# Sheet1.net
KiCad netlist of a schematic drawn in Altium Designer
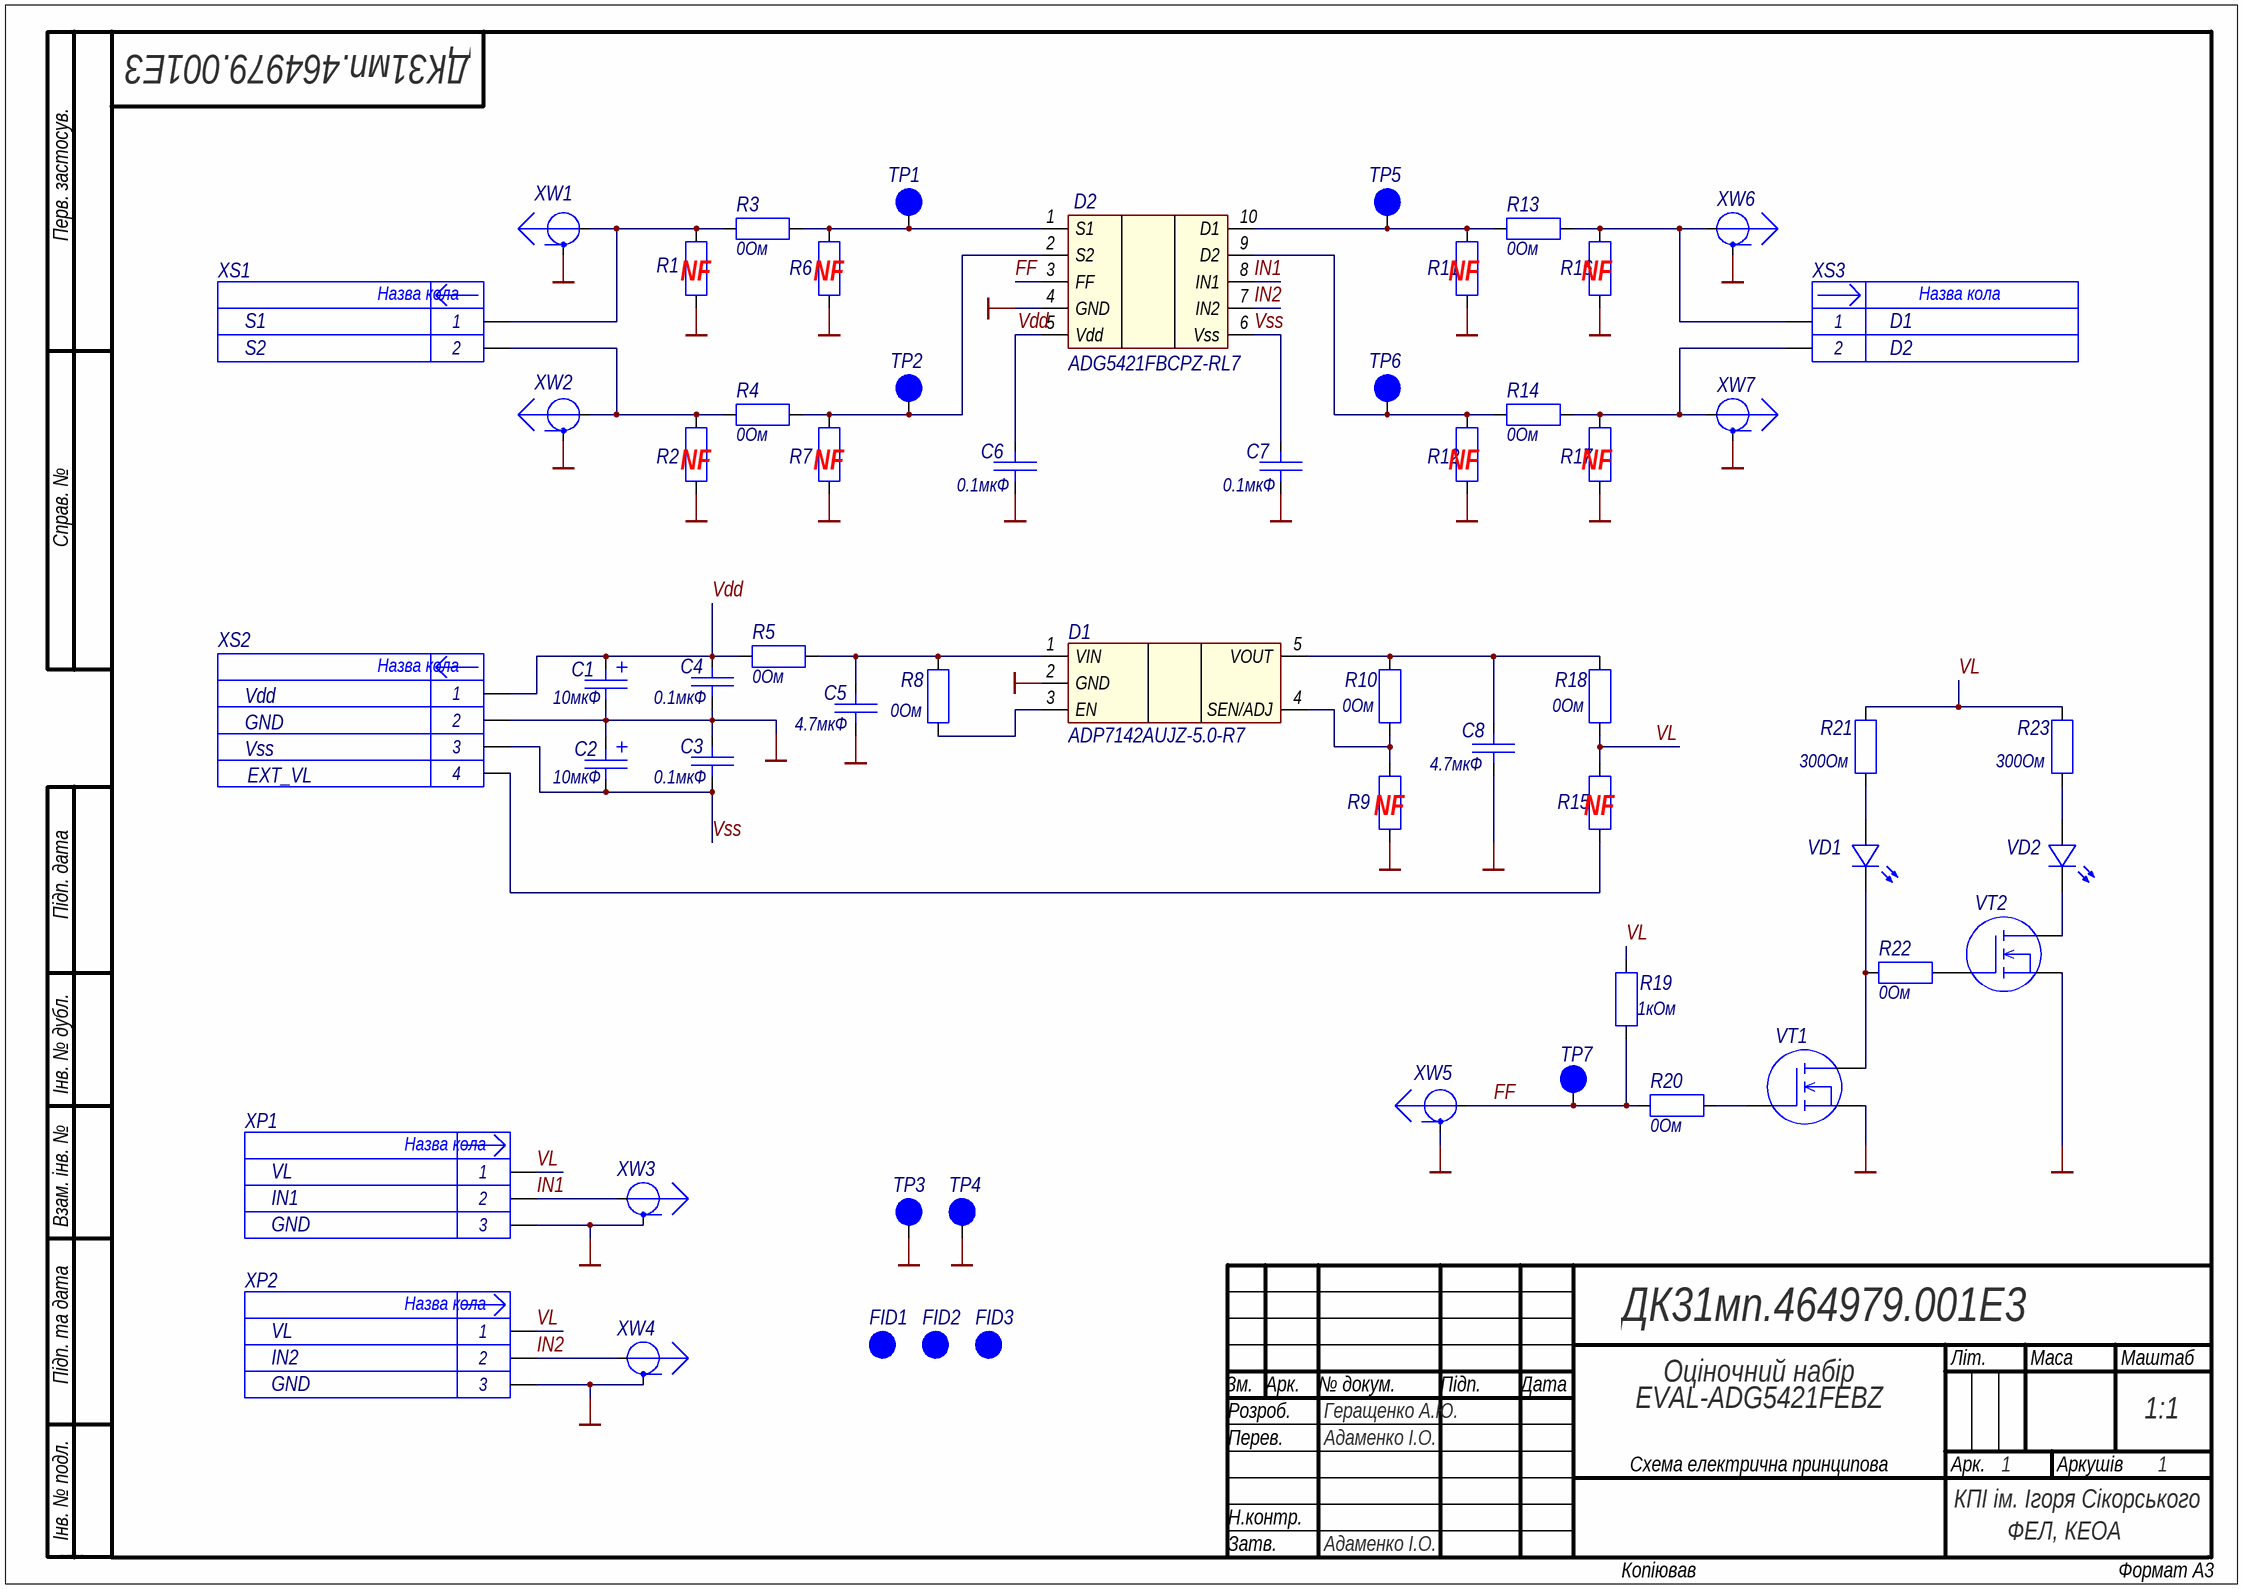
[diagram p0: Sheet1.SchDoc]

(export (version "E")
  (design (tool "Eeschema 10.0.6"))
  (components
    (comp (ref "C1")
      (value "10мкФ")
      (footprint "CAP_TANT_10uF")
      (description "CAP TANT 10UF 10% 50V 2917")
      (fields (field (name "MANUFACTURER") "KYOCERA AVX") (field (name "PART NUMBER") "478-2380-6-ND"))
      (libsource (lib "Schlib1") (part "CAP_TANT_10uF"))
    )
    (comp (ref "C2")
      (value "10мкФ")
      (footprint "CAP_TANT_10uF")
      (description "CAP TANT 10UF 10% 50V 2917")
      (fields (field (name "MANUFACTURER") "KYOCERA AVX") (field (name "PART NUMBER") "478-2380-6-ND"))
      (libsource (lib "Schlib1") (part "CAP_TANT_10uF"))
    )
    (comp (ref "C3")
      (value "0.1мкФ")
      (footprint "CAP_0603_0.1uF")
      (description "CAP CER 0.1UF 50V X7R 0603")
      (fields (field (name "MANUFACTURER") "Murata Electronics") (field (name "PART NUMBER") "490-1519-6-ND"))
      (libsource (lib "Schlib1") (part "CAP_0603_0.1uF"))
    )
    (comp (ref "C4")
      (value "0.1мкФ")
      (footprint "CAP_0603_0.1uF")
      (description "CAP CER 0.1UF 50V X7R 0603")
      (fields (field (name "MANUFACTURER") "Murata Electronics") (field (name "PART NUMBER") "490-1519-6-ND"))
      (libsource (lib "Schlib1") (part "CAP_0603_0.1uF"))
    )
    (comp (ref "C5")
      (value "4.7мкФ")
      (footprint "CAP_0805_4.7uF")
      (description "CAP CER 4.7UF 50V X5R 0805")
      (fields (field (name "MANUFACTURER") "TDK Corporation") (field (name "PART NUMBER") "445-5980-6-ND"))
      (libsource (lib "Schlib1") (part "CAP_0805_4.7uF"))
    )
    (comp (ref "C6")
      (value "0.1мкФ")
      (footprint "CAP_0603_0.1uF")
      (description "CAP CER 0.1UF 50V X7R 0603")
      (fields (field (name "MANUFACTURER") "Murata Electronics") (field (name "PART NUMBER") "490-1519-6-ND"))
      (libsource (lib "Schlib1") (part "CAP_0603_0.1uF"))
    )
    (comp (ref "C7")
      (value "0.1мкФ")
      (footprint "CAP_0603_0.1uF")
      (description "CAP CER 0.1UF 50V X7R 0603")
      (fields (field (name "MANUFACTURER") "Murata Electronics") (field (name "PART NUMBER") "490-1519-6-ND"))
      (libsource (lib "Schlib1") (part "CAP_0603_0.1uF"))
    )
    (comp (ref "C8")
      (value "4.7мкФ")
      (footprint "CAP_0805_4.7uF")
      (description "CAP CER 4.7UF 50V X5R 0805")
      (fields (field (name "MANUFACTURER") "TDK Corporation") (field (name "PART NUMBER") "445-5980-6-ND"))
      (libsource (lib "Schlib1") (part "CAP_0805_4.7uF"))
    )
    (comp (ref "D1")
      (value "ADP7142AUJZ-5.0-R7")
      (footprint "ADP7142AUJZ-5.0-R7")
      (description "IC REG LINEAR 5V 200MA TSOT23-5")
      (fields
        (field (name "MANUFACTURER") "Analog Devices Inc.")
        (field (name "PART NUMBER") "505-ADP7142AUJZ-5.0-R7DKR-ND")
      )
      (libsource (lib "Schlib1") (part "ADP7142AUJZ-5.0-R7"))
    )
    (comp (ref "D2")
      (value "ADG5421FBCPZ-RL7")
      (footprint "ADG5421FBCPZ-RL7")
      (description "IC SW SPST-NCX2 14OHM 10LFCSP")
      (fields
        (field (name "MANUFACTURER") "Analog Devices Inc.")
        (field (name "PART NUMBER") "505-ADG5421FBCPZ-RL7DKR-ND")
      )
      (libsource (lib "Schlib1") (part "ADG5421FBCPZ-RL7"))
    )
    (comp (ref "FID1")
      (value "Fiducial")
      (footprint "FIDUCIAL 1mm")
      (description "Fiducial 1mm Pad")
      (libsource (lib "Schlib1") (part "FIDUCIAL 1mm"))
    )
    (comp (ref "FID2")
      (value "Fiducial")
      (footprint "FIDUCIAL 1mm")
      (description "Fiducial 1mm Pad")
      (libsource (lib "Schlib1") (part "FIDUCIAL 1mm"))
    )
    (comp (ref "FID3")
      (value "Fiducial")
      (footprint "FIDUCIAL 1mm")
      (description "Fiducial 1mm Pad")
      (libsource (lib "Schlib1") (part "FIDUCIAL 1mm"))
    )
    (comp (ref "R1")
      (value "RES_0603 0Ohm")
      (footprint "RES_0603 0Ohm")
      (description "RES 0 OHM 63mW 0603")
      (fields (field (name "MANUFACTURER") "Multicomp") (field (name "PART NUMBER") "MC0603WG00000T5E-TC"))
      (libsource (lib "") (part "RES_0603 0Ohm_2"))
    )
    (comp (ref "R2")
      (value "RES_0603 0Ohm")
      (footprint "RES_0603 0Ohm")
      (description "RES 0 OHM 63mW 0603")
      (fields (field (name "MANUFACTURER") "Multicomp") (field (name "PART NUMBER") "MC0603WG00000T5E-TC"))
      (libsource (lib "") (part "RES_0603 0Ohm_2"))
    )
    (comp (ref "R3")
      (value "0Ом")
      (footprint "RES_0603 0Ohm")
      (description "RES 0 OHM 63mW 0603")
      (fields (field (name "MANUFACTURER") "Multicomp") (field (name "PART NUMBER") "MC0603WG00000T5E-TC"))
      (libsource (lib "") (part "RES_0603 0Ohm_1"))
    )
    (comp (ref "R4")
      (value "0Ом")
      (footprint "RES_0603 0Ohm")
      (description "RES 0 OHM 63mW 0603")
      (fields (field (name "MANUFACTURER") "Multicomp") (field (name "PART NUMBER") "MC0603WG00000T5E-TC"))
      (libsource (lib "") (part "RES_0603 0Ohm_1"))
    )
    (comp (ref "R5")
      (value "0Ом")
      (footprint "RES_0805 0Ohm")
      (description "RES SMD 0 OHM JUMPER 1/8W 0805")
      (fields
        (field (name "MANUFACTURER") "Panasonic Electronic Components")
        (field (name "PART NUMBER") "ERJ-6GEY0R00V")
      )
      (libsource (lib "Schlib1") (part "RES_0805 0Ohm"))
    )
    (comp (ref "R6")
      (value "RES_0603 0Ohm")
      (footprint "RES_0603 0Ohm")
      (description "RES 0 OHM 63mW 0603")
      (fields (field (name "MANUFACTURER") "Multicomp") (field (name "PART NUMBER") "MC0603WG00000T5E-TC"))
      (libsource (lib "") (part "RES_0603 0Ohm_2"))
    )
    (comp (ref "R7")
      (value "RES_0603 0Ohm")
      (footprint "RES_0603 0Ohm")
      (description "RES 0 OHM 63mW 0603")
      (fields (field (name "MANUFACTURER") "Multicomp") (field (name "PART NUMBER") "MC0603WG00000T5E-TC"))
      (libsource (lib "") (part "RES_0603 0Ohm_3"))
    )
    (comp (ref "R8")
      (value "0Ом")
      (footprint "RES_0603 0Ohm")
      (description "RES 0 OHM 63mW 0603")
      (fields (field (name "MANUFACTURER") "Multicomp") (field (name "PART NUMBER") "MC0603WG00000T5E-TC"))
      (libsource (lib "") (part "RES_0603 0Ohm_2"))
    )
    (comp (ref "R9")
      (value "RES_0603 0Ohm")
      (footprint "RES_0603 0Ohm")
      (description "RES 0 OHM 63mW 0603")
      (fields (field (name "MANUFACTURER") "Multicomp") (field (name "PART NUMBER") "MC0603WG00000T5E-TC"))
      (libsource (lib "") (part "RES_0603 0Ohm_2"))
    )
    (comp (ref "R10")
      (value "0Ом")
      (footprint "RES_0603 0Ohm")
      (description "RES 0 OHM 63mW 0603")
      (fields (field (name "MANUFACTURER") "Multicomp") (field (name "PART NUMBER") "MC0603WG00000T5E-TC"))
      (libsource (lib "") (part "RES_0603 0Ohm_2"))
    )
    (comp (ref "R11")
      (value "RES_0603 0Ohm")
      (footprint "RES_0603 0Ohm")
      (description "RES 0 OHM 63mW 0603")
      (fields (field (name "MANUFACTURER") "Multicomp") (field (name "PART NUMBER") "MC0603WG00000T5E-TC"))
      (libsource (lib "Schlib1") (part "RES_0603 0Ohm"))
    )
    (comp (ref "R12")
      (value "RES_0603 0Ohm")
      (footprint "RES_0603 0Ohm")
      (description "RES 0 OHM 63mW 0603")
      (fields (field (name "MANUFACTURER") "Multicomp") (field (name "PART NUMBER") "MC0603WG00000T5E-TC"))
      (libsource (lib "") (part "RES_0603 0Ohm_1"))
    )
    (comp (ref "R13")
      (value "0Ом")
      (footprint "RES_0603 0Ohm")
      (description "RES 0 OHM 63mW 0603")
      (fields (field (name "MANUFACTURER") "Multicomp") (field (name "PART NUMBER") "MC0603WG00000T5E-TC"))
      (libsource (lib "") (part "RES_0603 0Ohm_2"))
    )
    (comp (ref "R14")
      (value "0Ом")
      (footprint "RES_0603 0Ohm")
      (description "RES 0 OHM 63mW 0603")
      (fields (field (name "MANUFACTURER") "Multicomp") (field (name "PART NUMBER") "MC0603WG00000T5E-TC"))
      (libsource (lib "") (part "RES_0603 0Ohm_2"))
    )
    (comp (ref "R15")
      (value "RES_0805 0Ohm")
      (footprint "RES_0805 0Ohm")
      (description "RES SMD 0 OHM JUMPER 1/8W 0805")
      (fields
        (field (name "MANUFACTURER") "Panasonic Electronic Components")
        (field (name "PART NUMBER") "ERJ-6GEY0R00V")
      )
      (libsource (lib "") (part "RES_0805 0Ohm_1"))
    )
    (comp (ref "R16")
      (value "RES_0603 0Ohm")
      (footprint "RES_0603 0Ohm")
      (description "RES 0 OHM 63mW 0603")
      (fields (field (name "MANUFACTURER") "Multicomp") (field (name "PART NUMBER") "MC0603WG00000T5E-TC"))
      (libsource (lib "Schlib1") (part "RES_0603 0Ohm"))
    )
    (comp (ref "R17")
      (value "RES_0603 0Ohm")
      (footprint "RES_0603 0Ohm")
      (description "RES 0 OHM 63mW 0603")
      (fields (field (name "MANUFACTURER") "Multicomp") (field (name "PART NUMBER") "MC0603WG00000T5E-TC"))
      (libsource (lib "Schlib1") (part "RES_0603 0Ohm"))
    )
    (comp (ref "R18")
      (value "0Ом")
      (footprint "RES_0805 0Ohm")
      (description "RES SMD 0 OHM JUMPER 1/8W 0805")
      (fields
        (field (name "MANUFACTURER") "Panasonic Electronic Components")
        (field (name "PART NUMBER") "ERJ-6GEY0R00V")
      )
      (libsource (lib "") (part "RES_0805 0Ohm_1"))
    )
    (comp (ref "R19")
      (value "1кОм")
      (footprint "RES_0603 1kOhm")
      (description "RES 1K OHM 1% 63mW 0603")
      (fields (field (name "MANUFACTURER") "Multicomp") (field (name "PART NUMBER") "MC0063W060311K"))
      (libsource (lib "Schlib1") (part "RES_0603 1kOhm"))
    )
    (comp (ref "R20")
      (value "0Ом")
      (footprint "RES_0603 0Ohm")
      (description "RES 0 OHM 63mW 0603")
      (fields (field (name "MANUFACTURER") "Multicomp") (field (name "PART NUMBER") "MC0603WG00000T5E-TC"))
      (libsource (lib "Schlib1") (part "RES_0603 0Ohm"))
    )
    (comp (ref "R21")
      (value "300Ом")
      (footprint "RES_0805 300Ohm")
      (description "RES 300 OHM 5% 1/8W 0805")
      (fields (field (name "MANUFACTURER") "YAGEO") (field (name "PART NUMBER") "311-300ARDKR-ND"))
      (libsource (lib "Schlib1") (part "RES_0805 300Ohm"))
    )
    (comp (ref "R22")
      (value "0Ом")
      (footprint "RES_0603 0Ohm")
      (description "RES 0 OHM 63mW 0603")
      (fields (field (name "MANUFACTURER") "Multicomp") (field (name "PART NUMBER") "MC0603WG00000T5E-TC"))
      (libsource (lib "Schlib1") (part "RES_0603 0Ohm"))
    )
    (comp (ref "R23")
      (value "300Ом")
      (footprint "RES_0805 300Ohm")
      (description "RES 300 OHM 5% 1/8W 0805")
      (fields (field (name "MANUFACTURER") "YAGEO") (field (name "PART NUMBER") "311-300ARDKR-ND"))
      (libsource (lib "Schlib1") (part "RES_0805 300Ohm"))
    )
    (comp (ref "TP1")
      (value "Test point")
      (footprint "TEST POINT RED")
      (description "VERO 20-2137\r\nPCB Test Point, Red, Through Hole Mount, 1.02 mm, Phosphor Bronze")
      (libsource (lib "Schlib1") (part "TEST POINT RED"))
    )
    (comp (ref "TP2")
      (value "Test point")
      (footprint "TEST POINT RED")
      (description "VERO 20-2137\r\nPCB Test Point, Red, Through Hole Mount, 1.02 mm, Phosphor Bronze")
      (libsource (lib "Schlib1") (part "TEST POINT RED"))
    )
    (comp (ref "TP3")
      (value "Test point")
      (footprint "TEST POINT BLACK")
      (description "VERO 20-2137\r\nPCB Test Point, Black, Through Hole Mount, 1.02 mm, Phosphor Bronze")
      (libsource (lib "Schlib1") (part "TEST POINT BLACK"))
    )
    (comp (ref "TP4")
      (value "Test point")
      (footprint "TEST POINT BLACK")
      (description "VERO 20-2137\r\nPCB Test Point, Black, Through Hole Mount, 1.02 mm, Phosphor Bronze")
      (libsource (lib "Schlib1") (part "TEST POINT BLACK"))
    )
    (comp (ref "TP5")
      (value "Test point")
      (footprint "TEST POINT RED")
      (description "VERO 20-2137\r\nPCB Test Point, Red, Through Hole Mount, 1.02 mm, Phosphor Bronze")
      (libsource (lib "Schlib1") (part "TEST POINT RED"))
    )
    (comp (ref "TP6")
      (value "Test point")
      (footprint "TEST POINT RED")
      (description "VERO 20-2137\r\nPCB Test Point, Red, Through Hole Mount, 1.02 mm, Phosphor Bronze")
      (libsource (lib "Schlib1") (part "TEST POINT RED"))
    )
    (comp (ref "TP7")
      (value "Test point")
      (footprint "TEST POINT RED")
      (description "VERO 20-2137\r\nPCB Test Point, Red, Through Hole Mount, 1.02 mm, Phosphor Bronze")
      (libsource (lib "Schlib1") (part "TEST POINT RED"))
    )
    (comp (ref "VD1")
      (value "KP-2012SGC GREEN")
      (footprint "KP-2012SGC GREEN")
      (description "2-pin, SMT LED, green, forward voltage 2.2V, forward current 20mA")
      (fields (field (name "MANUFACTURER") "KINGBRIGHT") (field (name "PART NUMBER") "KP-2012SGC"))
      (libsource (lib "Schlib1") (part "KP-2012SGC GREEN"))
    )
    (comp (ref "VD2")
      (value "KP-2012EC RED")
      (footprint "KP-2012EC RED")
      (description "2-pin, SMT LED, red, forward voltage 2V, forward current 20mA")
      (fields (field (name "MANUFACTURER") "KINGBRIGHT") (field (name "PART NUMBER") "KP-2012EC"))
      (libsource (lib "Schlib1") (part "KP-2012EC RED"))
    )
    (comp (ref "VT1")
      (value "NDS7002A onsemi")
      (footprint "NDS7002A")
      (description "MOSFET N-CH 60V 280MA SOT-23")
      (fields (field (name "MANUFACTURER") "onsemi"))
      (libsource (lib "Schlib1") (part "NDS7002A"))
    )
    (comp (ref "VT2")
      (value "NDS7002A onsemi")
      (footprint "NDS7002A")
      (description "MOSFET N-CH 60V 280MA SOT-23")
      (fields (field (name "MANUFACTURER") "onsemi"))
      (libsource (lib "Schlib1") (part "NDS7002A"))
    )
    (comp (ref "XP1")
      (value "M20-9990345")
      (footprint "M20-9990345")
      (description "CONN HEADER VERT 3POS 2.54MM")
      (fields (field (name "MANUFACTURER") "Harwin Inc.") (field (name "PART NUMBER") "952-2263-ND"))
      (libsource (lib "Schlib1") (part "M20-9990345"))
    )
    (comp (ref "XP2")
      (value "M20-9990345")
      (footprint "M20-9990345")
      (description "CONN HEADER VERT 3POS 2.54MM")
      (fields (field (name "MANUFACTURER") "Harwin Inc.") (field (name "PART NUMBER") "952-2263-ND"))
      (libsource (lib "Schlib1") (part "M20-9990345"))
    )
    (comp (ref "XS1")
      (value "CTB5000/2")
      (footprint "CTB5000/2")
      (description "2-pin, terminal blocks (5 mm pitch), 250V, 16A")
      (fields (field (name "MANUFACTURER") "CAMDENBOSS"))
      (libsource (lib "") (part "CTB5000/2_1"))
    )
    (comp (ref "XS2")
      (value "CTB5000/4")
      (footprint "CTB5000/4")
      (description "4-pin, terminal blocks (5 mm pitch), 250V, 16A")
      (fields (field (name "MANUFACTURER") "CAMDENBOSS"))
      (libsource (lib "Schlib1") (part "CTB5000/4"))
    )
    (comp (ref "XS3")
      (value "CTB5000/2")
      (footprint "CTB5000/2")
      (description "2-pin, terminal blocks (5 mm pitch), 250V, 16A")
      (fields (field (name "MANUFACTURER") "CAMDENBOSS"))
      (libsource (lib "Schlib1") (part "CTB5000/2"))
    )
    (comp (ref "XW1")
      (value "SMB1251B1-3GT30G-50")
      (footprint "SMB1251B1-3GT30G-50")
      (description "50 Ω, SMB connectors")
      (fields (field (name "MANUFACTURER") "AMPHENOL RF"))
      (libsource (lib "") (part "SMB1251B1-3GT30G-50_1"))
    )
    (comp (ref "XW2")
      (value "SMB1251B1-3GT30G-50")
      (footprint "SMB1251B1-3GT30G-50")
      (description "50 Ω, SMB connectors")
      (fields (field (name "MANUFACTURER") "AMPHENOL RF"))
      (libsource (lib "Schlib1") (part "SMB1251B1-3GT30G-50"))
    )
    (comp (ref "XW3")
      (value "SMB1251B1-3GT30G-50")
      (footprint "SMB1251B1-3GT30G-50")
      (description "50 Ω, SMB connectors")
      (fields (field (name "MANUFACTURER") "AMPHENOL RF"))
      (libsource (lib "Schlib1") (part "SMB1251B1-3GT30G-50"))
    )
    (comp (ref "XW4")
      (value "SMB1251B1-3GT30G-50")
      (footprint "SMB1251B1-3GT30G-50")
      (description "50 Ω, SMB connectors")
      (fields (field (name "MANUFACTURER") "AMPHENOL RF"))
      (libsource (lib "Schlib1") (part "SMB1251B1-3GT30G-50"))
    )
    (comp (ref "XW5")
      (value "SMB1251B1-3GT30G-50")
      (footprint "SMB1251B1-3GT30G-50")
      (description "50 Ω, SMB connectors")
      (fields (field (name "MANUFACTURER") "AMPHENOL RF"))
      (libsource (lib "Schlib1") (part "SMB1251B1-3GT30G-50"))
    )
    (comp (ref "XW6")
      (value "SMB1251B1-3GT30G-50")
      (footprint "SMB1251B1-3GT30G-50")
      (description "50 Ω, SMB connectors")
      (fields (field (name "MANUFACTURER") "AMPHENOL RF"))
      (libsource (lib "") (part "SMB1251B1-3GT30G-50_1"))
    )
    (comp (ref "XW7")
      (value "SMB1251B1-3GT30G-50")
      (footprint "SMB1251B1-3GT30G-50")
      (description "50 Ω, SMB connectors")
      (fields (field (name "MANUFACTURER") "AMPHENOL RF"))
      (libsource (lib "Schlib1") (part "SMB1251B1-3GT30G-50"))
    )
  )
  (nets
    (net (code "1") (name "/FF") (class "Default")
      (node (ref "D2") (pin "3") (pinfunction "FF_3") (pintype "passive"))
      (node (ref "R19") (pin "1") (pinfunction "1_1") (pintype "passive"))
      (node (ref "R20") (pin "1") (pinfunction "1_1") (pintype "passive"))
      (node (ref "TP7") (pin "1") (pinfunction "1_1") (pintype "passive"))
      (node (ref "XW5") (pin "1") (pintype "passive"))
    )
    (net (code "2") (name "/IN1") (class "Default")
      (node (ref "D2") (pin "8") (pinfunction "IN1_8") (pintype "passive"))
      (node (ref "XP1") (pin "2") (pinfunction "2_2") (pintype "passive"))
      (node (ref "XW3") (pin "1") (pintype "passive"))
    )
    (net (code "3") (name "/IN2") (class "Default")
      (node (ref "D2") (pin "7") (pinfunction "IN2_7") (pintype "passive"))
      (node (ref "XP2") (pin "2") (pinfunction "2_2") (pintype "passive"))
      (node (ref "XW4") (pin "1") (pintype "passive"))
    )
    (net (code "4") (name "/VL") (class "Default")
      (node (ref "R15") (pin "2") (pinfunction "2_2") (pintype "passive"))
      (node (ref "R18") (pin "1") (pinfunction "1_1") (pintype "passive"))
      (node (ref "R19") (pin "2") (pinfunction "2_2") (pintype "passive"))
      (node (ref "R21") (pin "2") (pinfunction "2_2") (pintype "passive"))
      (node (ref "R23") (pin "2") (pinfunction "2_2") (pintype "passive"))
      (node (ref "XP1") (pin "1") (pinfunction "1_1") (pintype "passive"))
      (node (ref "XP2") (pin "1") (pinfunction "1_1") (pintype "passive"))
    )
    (net (code "5") (name "/Vdd") (class "Default")
      (node (ref "C1") (pin "1") (pinfunction "1_1") (pintype "passive"))
      (node (ref "C4") (pin "2") (pinfunction "2_2") (pintype "passive"))
      (node (ref "C6") (pin "2") (pinfunction "2_2") (pintype "passive"))
      (node (ref "D2") (pin "5") (pinfunction "Vdd_5") (pintype "passive"))
      (node (ref "R5") (pin "1") (pinfunction "1_1") (pintype "passive"))
      (node (ref "XS2") (pin "1") (pinfunction "1_1") (pintype "passive"))
    )
    (net (code "6") (name "/Vss") (class "Default")
      (node (ref "C2") (pin "2") (pinfunction "2_2") (pintype "passive"))
      (node (ref "C3") (pin "1") (pinfunction "1_1") (pintype "passive"))
      (node (ref "C7") (pin "2") (pinfunction "2_2") (pintype "passive"))
      (node (ref "D2") (pin "6") (pinfunction "Vss_6") (pintype "passive"))
      (node (ref "XS2") (pin "3") (pinfunction "3_3") (pintype "passive"))
    )
    (net (code "7") (name "GND") (class "Default")
      (node (ref "C1") (pin "2") (pinfunction "2_2") (pintype "passive"))
      (node (ref "C2") (pin "1") (pinfunction "1_1") (pintype "passive"))
      (node (ref "C3") (pin "2") (pinfunction "2_2") (pintype "passive"))
      (node (ref "C4") (pin "1") (pinfunction "1_1") (pintype "passive"))
      (node (ref "C5") (pin "1") (pinfunction "1_1") (pintype "passive"))
      (node (ref "C6") (pin "1") (pinfunction "1_1") (pintype "passive"))
      (node (ref "C7") (pin "1") (pinfunction "1_1") (pintype "passive"))
      (node (ref "C8") (pin "1") (pinfunction "1_1") (pintype "passive"))
      (node (ref "D1") (pin "2") (pinfunction "GND_2") (pintype "passive"))
      (node (ref "D2") (pin "4") (pinfunction "GND_4") (pintype "passive"))
      (node (ref "R1") (pin "1") (pinfunction "1_1") (pintype "passive"))
      (node (ref "R11") (pin "1") (pinfunction "1_1") (pintype "passive"))
      (node (ref "R12") (pin "2") (pinfunction "2_2") (pintype "passive"))
      (node (ref "R16") (pin "1") (pinfunction "1_1") (pintype "passive"))
      (node (ref "R17") (pin "1") (pinfunction "1_1") (pintype "passive"))
      (node (ref "R2") (pin "1") (pinfunction "1_1") (pintype "passive"))
      (node (ref "R6") (pin "1") (pinfunction "1_1") (pintype "passive"))
      (node (ref "R7") (pin "2") (pinfunction "2_2") (pintype "passive"))
      (node (ref "R9") (pin "1") (pinfunction "1_1") (pintype "passive"))
      (node (ref "TP3") (pin "1") (pinfunction "1_1") (pintype "passive"))
      (node (ref "TP4") (pin "1") (pinfunction "1_1") (pintype "passive"))
      (node (ref "VT1") (pin "2") (pinfunction "2_2") (pintype "passive"))
      (node (ref "VT2") (pin "2") (pinfunction "2_2") (pintype "passive"))
      (node (ref "XP1") (pin "3") (pinfunction "3_3") (pintype "passive"))
      (node (ref "XP2") (pin "3") (pinfunction "3_3") (pintype "passive"))
      (node (ref "XS2") (pin "2") (pinfunction "2_2") (pintype "passive"))
      (node (ref "XW1") (pin "2") (pintype "passive"))
      (node (ref "XW2") (pin "2") (pintype "passive"))
      (node (ref "XW3") (pin "2") (pintype "passive"))
      (node (ref "XW4") (pin "2") (pintype "passive"))
      (node (ref "XW5") (pin "2") (pintype "passive"))
      (node (ref "XW6") (pin "2") (pintype "passive"))
      (node (ref "XW7") (pin "2") (pintype "passive"))
    )
    (net (code "8") (name "Net-(D1-EN)") (class "Default")
      (node (ref "D1") (pin "3") (pinfunction "EN_3") (pintype "passive"))
      (node (ref "R8") (pin "1") (pinfunction "1_1") (pintype "passive"))
    )
    (net (code "9") (name "Net-(D1-SEN{slash}ADJ)") (class "Default")
      (node (ref "D1") (pin "4") (pinfunction "SEN/ADJ_4") (pintype "passive"))
      (node (ref "R10") (pin "1") (pinfunction "1_1") (pintype "passive"))
      (node (ref "R9") (pin "2") (pinfunction "2_2") (pintype "passive"))
    )
    (net (code "10") (name "Net-(D1-VIN)") (class "Default")
      (node (ref "C5") (pin "2") (pinfunction "2_2") (pintype "passive"))
      (node (ref "D1") (pin "1") (pinfunction "VIN_1") (pintype "passive"))
      (node (ref "R5") (pin "2") (pinfunction "2_2") (pintype "passive"))
      (node (ref "R8") (pin "2") (pinfunction "2_2") (pintype "passive"))
    )
    (net (code "11") (name "Net-(D1-VOUT)") (class "Default")
      (node (ref "C8") (pin "2") (pinfunction "2_2") (pintype "passive"))
      (node (ref "D1") (pin "5") (pinfunction "VOUT_5") (pintype "passive"))
      (node (ref "R10") (pin "2") (pinfunction "2_2") (pintype "passive"))
      (node (ref "R18") (pin "2") (pinfunction "2_2") (pintype "passive"))
    )
    (net (code "12") (name "Net-(D2-D1)") (class "Default")
      (node (ref "D2") (pin "10") (pinfunction "D1_10") (pintype "passive"))
      (node (ref "R11") (pin "2") (pinfunction "2_2") (pintype "passive"))
      (node (ref "R13") (pin "1") (pinfunction "1_1") (pintype "passive"))
      (node (ref "TP5") (pin "1") (pinfunction "1_1") (pintype "passive"))
    )
    (net (code "13") (name "Net-(D2-D2)") (class "Default")
      (node (ref "D2") (pin "9") (pinfunction "D2_9") (pintype "passive"))
      (node (ref "R12") (pin "1") (pinfunction "1_1") (pintype "passive"))
      (node (ref "R14") (pin "1") (pinfunction "1_1") (pintype "passive"))
      (node (ref "TP6") (pin "1") (pinfunction "1_1") (pintype "passive"))
    )
    (net (code "14") (name "Net-(D2-S1)") (class "Default")
      (node (ref "D2") (pin "1") (pinfunction "S1_1") (pintype "passive"))
      (node (ref "R3") (pin "1") (pinfunction "1_1") (pintype "passive"))
      (node (ref "R6") (pin "2") (pinfunction "2_2") (pintype "passive"))
      (node (ref "TP1") (pin "1") (pinfunction "1_1") (pintype "passive"))
    )
    (net (code "15") (name "Net-(D2-S2)") (class "Default")
      (node (ref "D2") (pin "2") (pinfunction "S2_2") (pintype "passive"))
      (node (ref "R4") (pin "1") (pinfunction "1_1") (pintype "passive"))
      (node (ref "R7") (pin "1") (pinfunction "1_1") (pintype "passive"))
      (node (ref "TP2") (pin "1") (pinfunction "1_1") (pintype "passive"))
    )
    (net (code "16") (name "Net-(R1-Pad2)") (class "Default")
      (node (ref "R1") (pin "2") (pinfunction "2_2") (pintype "passive"))
      (node (ref "R3") (pin "2") (pinfunction "2_2") (pintype "passive"))
      (node (ref "XS1") (pin "2") (pinfunction "2_2") (pintype "passive"))
      (node (ref "XW1") (pin "1") (pintype "passive"))
    )
    (net (code "17") (name "Net-(R2-Pad2)") (class "Default")
      (node (ref "R2") (pin "2") (pinfunction "2_2") (pintype "passive"))
      (node (ref "R4") (pin "2") (pinfunction "2_2") (pintype "passive"))
      (node (ref "XS1") (pin "1") (pinfunction "1_1") (pintype "passive"))
      (node (ref "XW2") (pin "1") (pintype "passive"))
    )
    (net (code "18") (name "Net-(R13-Pad2)") (class "Default")
      (node (ref "R13") (pin "2") (pinfunction "2_2") (pintype "passive"))
      (node (ref "R16") (pin "2") (pinfunction "2_2") (pintype "passive"))
      (node (ref "XS3") (pin "1") (pinfunction "1_1") (pintype "passive"))
      (node (ref "XW6") (pin "1") (pintype "passive"))
    )
    (net (code "19") (name "Net-(R14-Pad2)") (class "Default")
      (node (ref "R14") (pin "2") (pinfunction "2_2") (pintype "passive"))
      (node (ref "R17") (pin "2") (pinfunction "2_2") (pintype "passive"))
      (node (ref "XS3") (pin "2") (pinfunction "2_2") (pintype "passive"))
      (node (ref "XW7") (pin "1") (pintype "passive"))
    )
    (net (code "20") (name "Net-(R15-Pad1)") (class "Default")
      (node (ref "R15") (pin "1") (pinfunction "1_1") (pintype "passive"))
      (node (ref "XS2") (pin "4") (pinfunction "4_4") (pintype "passive"))
    )
    (net (code "21") (name "Net-(R20-Pad2)") (class "Default")
      (node (ref "R20") (pin "2") (pinfunction "2_2") (pintype "passive"))
      (node (ref "VT1") (pin "1") (pinfunction "1_1") (pintype "passive"))
    )
    (net (code "22") (name "Net-(R21-Pad1)") (class "Default")
      (node (ref "R21") (pin "1") (pinfunction "1_1") (pintype "passive"))
      (node (ref "VD1") (pin "1") (pinfunction "1_1") (pintype "passive"))
    )
    (net (code "23") (name "Net-(R22-Pad1)") (class "Default")
      (node (ref "R22") (pin "1") (pinfunction "1_1") (pintype "passive"))
      (node (ref "VD1") (pin "2") (pinfunction "2_2") (pintype "passive"))
      (node (ref "VT1") (pin "3") (pinfunction "3_3") (pintype "passive"))
    )
    (net (code "24") (name "Net-(R22-Pad2)") (class "Default")
      (node (ref "R22") (pin "2") (pinfunction "2_2") (pintype "passive"))
      (node (ref "VT2") (pin "1") (pinfunction "1_1") (pintype "passive"))
    )
    (net (code "25") (name "Net-(R23-Pad1)") (class "Default")
      (node (ref "R23") (pin "1") (pinfunction "1_1") (pintype "passive"))
      (node (ref "VD2") (pin "1") (pinfunction "1_1") (pintype "passive"))
    )
    (net (code "26") (name "Net-(VD2-Pad2)") (class "Default")
      (node (ref "VD2") (pin "2") (pinfunction "2_2") (pintype "passive"))
      (node (ref "VT2") (pin "3") (pinfunction "3_3") (pintype "passive"))
    )
  )
)
